# SpaceInvaders-v21.net
KiCad netlist of a schematic drawn in EAGLE
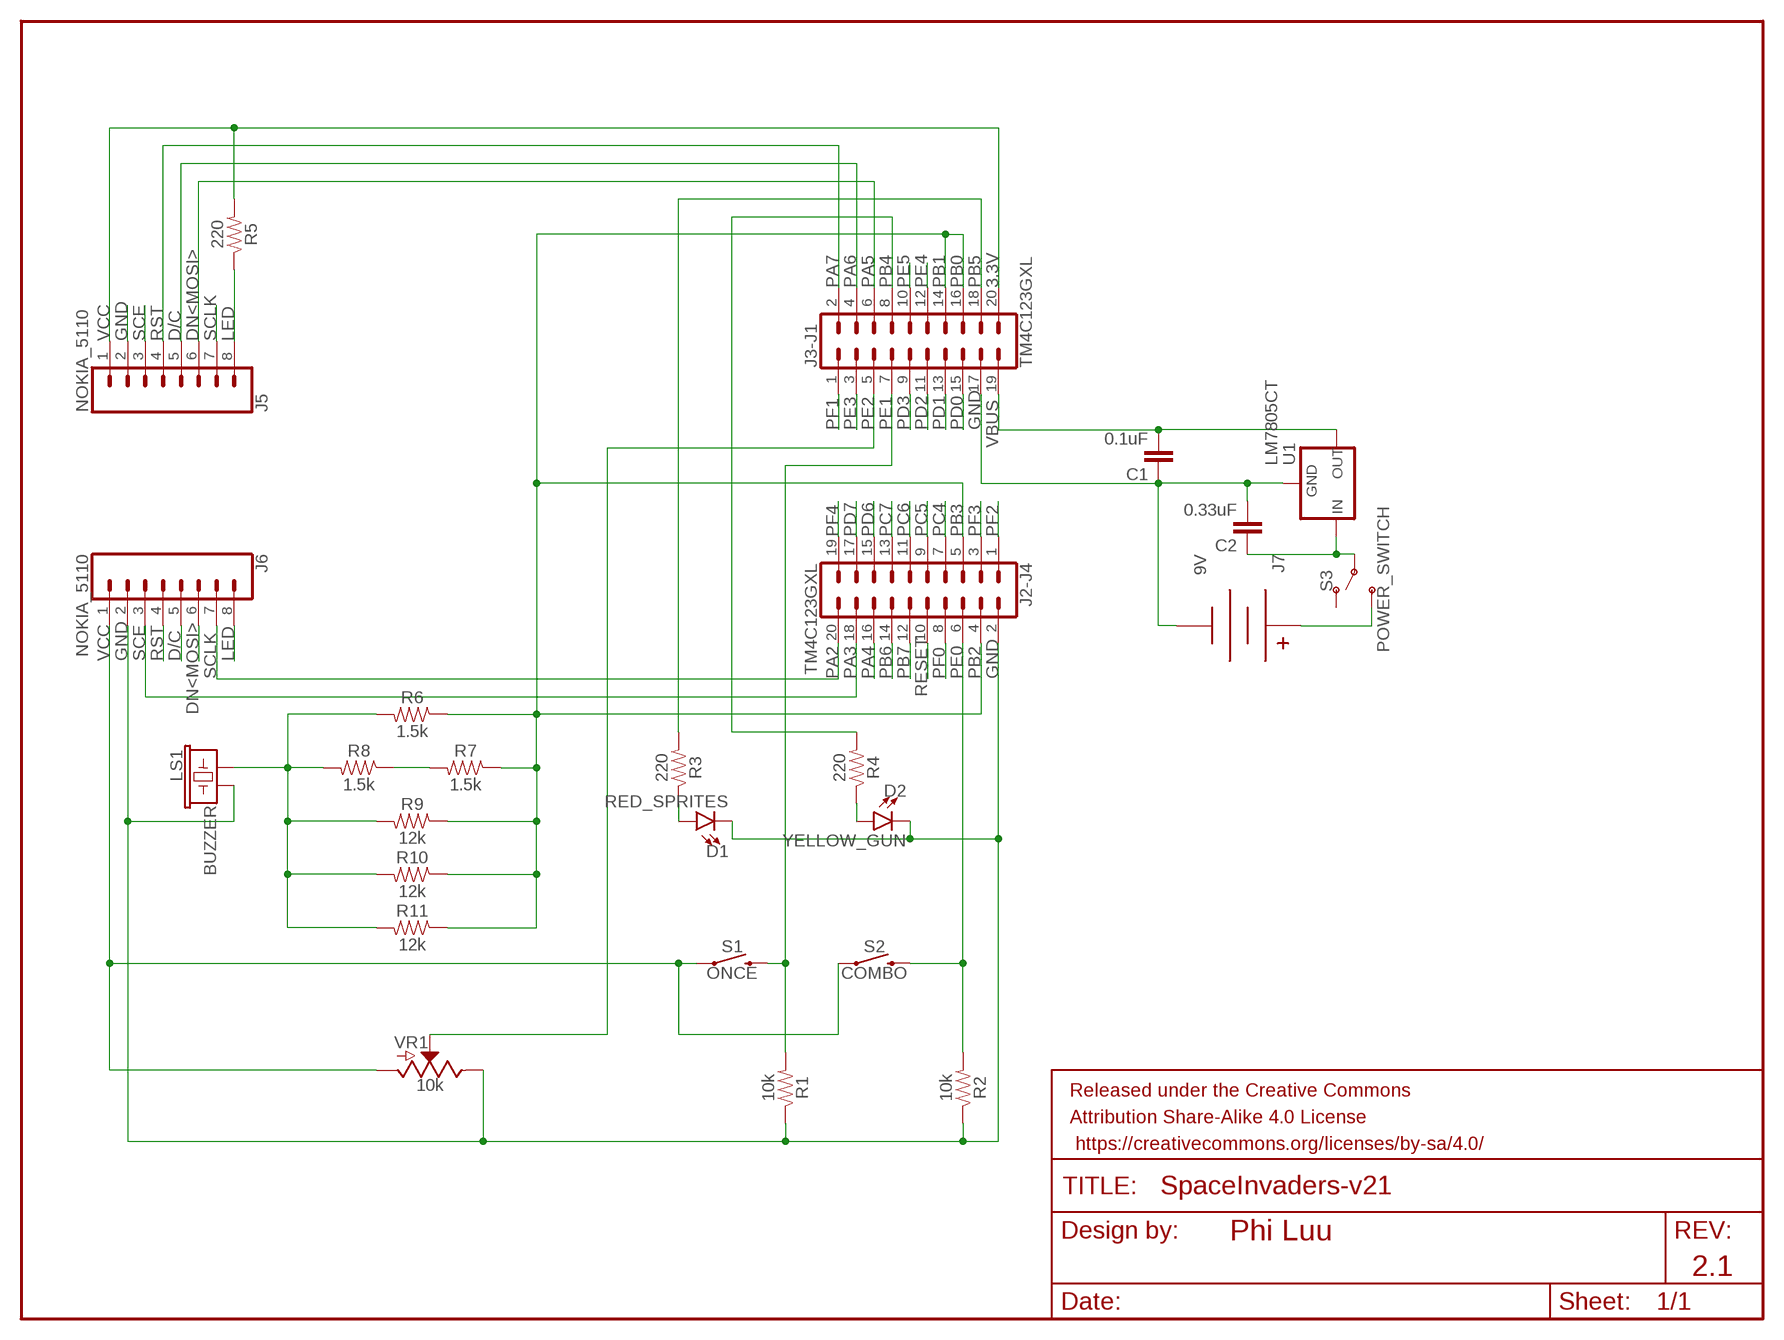
[diagram p0: schematic, sheet 1]

(export (version "E")
  (design (tool "Eeschema 10.0.6"))
  (components
    (comp (ref "C1")
      (value "0.1uF")
      (footprint "eagle-import:CAP-PTH-SMALL-KIT")
      (libsource (lib "eagle-import") (part "0.1UF-KIT-EZ-50V-20%"))
    )
    (comp (ref "C2")
      (value "0.33uF")
      (footprint "eagle-import:CAP-PTH-SMALL-KIT")
      (libsource (lib "eagle-import") (part "0.1UF-KIT-EZ-50V-20%"))
    )
    (comp (ref "D1")
      (value "RED_SPRITES")
      (footprint "eagle-import:LED_5MM")
      (libsource (lib "eagle-import") (part "LED5MM"))
    )
    (comp (ref "D2")
      (value "YELLOW_GUN")
      (footprint "eagle-import:LED_5MM")
      (libsource (lib "eagle-import") (part "LED5MM"))
    )
    (comp (ref "FRAME1")
      (value "FRAME-LETTER")
      (footprint "eagle-import:CREATIVE_COMMONS")
      (libsource (lib "eagle-import") (part "FRAME-LETTER"))
    )
    (comp (ref "J2-J4")
      (value "TM4C123GXL")
      (footprint "eagle-import:2X10")
      (libsource (lib "eagle-import") (part "CONN_10X2"))
    )
    (comp (ref "J3-J1")
      (value "TM4C123GXL")
      (footprint "eagle-import:2X10")
      (libsource (lib "eagle-import") (part "CONN_10X2"))
    )
    (comp (ref "J5")
      (value "NOKIA_5110")
      (footprint "eagle-import:1X08")
      (libsource (lib "eagle-import") (part "CONN_08{dblquote}"))
    )
    (comp (ref "J6")
      (value "NOKIA_5110")
      (footprint "eagle-import:1X08")
      (libsource (lib "eagle-import") (part "CONN_08{dblquote}"))
    )
    (comp (ref "J7")
      (value "9V")
      (footprint "eagle-import:BC9VPC")
      (libsource (lib "eagle-import") (part "BC9VPC"))
    )
    (comp (ref "LS1")
      (value "BUZZER")
      (footprint "eagle-import:BUZZER-12MM")
      (libsource (lib "eagle-import") (part "BUZZER-PTH"))
    )
    (comp (ref "R1")
      (value "10k")
      (footprint "eagle-import:AXIAL-0.3")
      (libsource (lib "eagle-import") (part "10KOHM-HORIZ-1/4W-5%"))
    )
    (comp (ref "R2")
      (value "10k")
      (footprint "eagle-import:AXIAL-0.3")
      (libsource (lib "eagle-import") (part "10KOHM-HORIZ-1/4W-5%"))
    )
    (comp (ref "R3")
      (value "220")
      (footprint "eagle-import:AXIAL-0.3")
      (libsource (lib "eagle-import") (part "1KOHM-HORIZ-1/4W-5%"))
    )
    (comp (ref "R4")
      (value "220")
      (footprint "eagle-import:AXIAL-0.3")
      (libsource (lib "eagle-import") (part "1KOHM-HORIZ-1/4W-5%"))
    )
    (comp (ref "R5")
      (value "220")
      (footprint "eagle-import:AXIAL-0.3")
      (libsource (lib "eagle-import") (part "1KOHM-HORIZ-1/4W-5%"))
    )
    (comp (ref "R6")
      (value "1.5k")
      (footprint "eagle-import:AXIAL-0.3")
      (libsource (lib "eagle-import") (part "1KOHM-HORIZ-1/4W-5%"))
    )
    (comp (ref "R7")
      (value "1.5k")
      (footprint "eagle-import:AXIAL-0.3")
      (libsource (lib "eagle-import") (part "1KOHM-HORIZ-1/4W-5%"))
    )
    (comp (ref "R8")
      (value "1.5k")
      (footprint "eagle-import:AXIAL-0.3")
      (libsource (lib "eagle-import") (part "1KOHM-HORIZ-1/4W-5%"))
    )
    (comp (ref "R9")
      (value "12k")
      (footprint "eagle-import:AXIAL-0.3")
      (libsource (lib "eagle-import") (part "1KOHM-HORIZ-1/4W-5%"))
    )
    (comp (ref "R10")
      (value "12k")
      (footprint "eagle-import:AXIAL-0.3")
      (libsource (lib "eagle-import") (part "1KOHM-HORIZ-1/4W-5%"))
    )
    (comp (ref "R11")
      (value "12k")
      (footprint "eagle-import:AXIAL-0.3")
      (libsource (lib "eagle-import") (part "1KOHM-HORIZ-1/4W-5%"))
    )
    (comp (ref "S1")
      (value "ONCE")
      (footprint "eagle-import:TACTILE_SWITCH_PTH_6.0MM")
      (libsource (lib "eagle-import") (part "MOMENTARY-SWITCH-SPST-PTH-6.0MM"))
    )
    (comp (ref "S2")
      (value "COMBO")
      (footprint "eagle-import:TACTILE_SWITCH_PTH_6.0MM")
      (libsource (lib "eagle-import") (part "MOMENTARY-SWITCH-SPST-PTH-6.0MM"))
    )
    (comp (ref "S3")
      (value "POWER_SWITCH")
      (footprint "eagle-import:SWITCH_SPDT_PTH_11.6X4.0MM")
      (libsource (lib "eagle-import") (part "SWITCH-SPDT-PTH-11.6X4.0MM"))
    )
    (comp (ref "U1")
      (value "LM7805CT")
      (footprint "eagle-import:TO220-IGO")
      (libsource (lib "eagle-import") (part "V_REG_78XXSINK"))
    )
    (comp (ref "VR1")
      (value "10k")
      (footprint "eagle-import:SLIDER-MEDIUM")
      (libsource (lib "eagle-import") (part "POTENTIOMETER_SLIDE-30MM-1/10W-20%"))
    )
  )
  (nets
    (net (code "1") (name "/3.3V") (class "Default")
      (node (ref "J3-J1") (pin "20") (pinfunction "20_20") (pintype "passive"))
      (node (ref "J5") (pin "1") (pinfunction "1_1") (pintype "passive"))
      (node (ref "J6") (pin "1") (pinfunction "1_1") (pintype "passive"))
      (node (ref "R5") (pin "P$2") (pinfunction "2_P$2") (pintype "passive"))
      (node (ref "S1") (pin "1") (pinfunction "1_1") (pintype "passive"))
      (node (ref "S2") (pin "1") (pinfunction "1_1") (pintype "passive"))
      (node (ref "VR1") (pin "BOTTOM") (pinfunction "A_BOTTOM") (pintype "passive"))
    )
    (net (code "2") (name "/GND") (class "Default")
      (node (ref "C1") (pin "1") (pinfunction "1_1") (pintype "passive"))
      (node (ref "C2") (pin "2") (pinfunction "2_2") (pintype "passive"))
      (node (ref "D1") (pin "K") (pinfunction "C_K") (pintype "passive"))
      (node (ref "D2") (pin "K") (pinfunction "C_K") (pintype "passive"))
      (node (ref "J2-J4") (pin "2") (pinfunction "2_2") (pintype "passive"))
      (node (ref "J3-J1") (pin "17") (pinfunction "17_17") (pintype "passive"))
      (node (ref "J5") (pin "2") (pinfunction "2_2") (pintype "passive"))
      (node (ref "J6") (pin "2") (pinfunction "2_2") (pintype "passive"))
      (node (ref "J7") (pin "V-") (pinfunction "V-_V-") (pintype "bidirectional"))
      (node (ref "LS1") (pin "-") (pinfunction "2_-") (pintype "passive"))
      (node (ref "R1") (pin "P$1") (pinfunction "1_P$1") (pintype "passive"))
      (node (ref "R2") (pin "P$1") (pinfunction "1_P$1") (pintype "passive"))
      (node (ref "U1") (pin "GND") (pinfunction "GND_GND") (pintype "input"))
      (node (ref "VR1") (pin "TOP") (pinfunction "E_TOP") (pintype "passive"))
    )
    (net (code "3") (name "/LED") (class "Default")
      (node (ref "J5") (pin "8") (pinfunction "8_8") (pintype "passive"))
      (node (ref "J6") (pin "8") (pinfunction "8_8") (pintype "passive"))
      (node (ref "R5") (pin "P$1") (pinfunction "1_P$1") (pintype "passive"))
    )
    (net (code "4") (name "/PA2") (class "Default")
      (node (ref "J2-J4") (pin "20") (pinfunction "20_20") (pintype "passive"))
      (node (ref "J5") (pin "7") (pinfunction "7_7") (pintype "passive"))
      (node (ref "J6") (pin "7") (pinfunction "7_7") (pintype "passive"))
    )
    (net (code "5") (name "/PA3") (class "Default")
      (node (ref "J2-J4") (pin "18") (pinfunction "18_18") (pintype "passive"))
      (node (ref "J5") (pin "3") (pinfunction "3_3") (pintype "passive"))
      (node (ref "J6") (pin "3") (pinfunction "3_3") (pintype "passive"))
    )
    (net (code "6") (name "/PA4") (class "Default")
      (node (ref "J2-J4") (pin "16") (pinfunction "16_16") (pintype "passive"))
    )
    (net (code "7") (name "/PA5") (class "Default")
      (node (ref "J3-J1") (pin "6") (pinfunction "6_6") (pintype "passive"))
      (node (ref "J5") (pin "6") (pinfunction "6_6") (pintype "passive"))
      (node (ref "J6") (pin "6") (pinfunction "6_6") (pintype "passive"))
    )
    (net (code "8") (name "/PA6") (class "Default")
      (node (ref "J3-J1") (pin "4") (pinfunction "4_4") (pintype "passive"))
      (node (ref "J5") (pin "5") (pinfunction "5_5") (pintype "passive"))
      (node (ref "J6") (pin "5") (pinfunction "5_5") (pintype "passive"))
    )
    (net (code "9") (name "/PA7") (class "Default")
      (node (ref "J3-J1") (pin "2") (pinfunction "2_2") (pintype "passive"))
      (node (ref "J5") (pin "4") (pinfunction "4_4") (pintype "passive"))
      (node (ref "J6") (pin "4") (pinfunction "4_4") (pintype "passive"))
    )
    (net (code "10") (name "/PB4") (class "Default")
      (node (ref "J3-J1") (pin "8") (pinfunction "8_8") (pintype "passive"))
      (node (ref "R4") (pin "P$2") (pinfunction "2_P$2") (pintype "passive"))
    )
    (net (code "11") (name "/PB5") (class "Default")
      (node (ref "J3-J1") (pin "18") (pinfunction "18_18") (pintype "passive"))
      (node (ref "R3") (pin "P$2") (pinfunction "2_P$2") (pintype "passive"))
    )
    (net (code "12") (name "/PB6") (class "Default")
      (node (ref "J2-J4") (pin "14") (pinfunction "14_14") (pintype "passive"))
    )
    (net (code "13") (name "/PB7") (class "Default")
      (node (ref "J2-J4") (pin "12") (pinfunction "12_12") (pintype "passive"))
    )
    (net (code "14") (name "/PC4") (class "Default")
      (node (ref "J2-J4") (pin "7") (pinfunction "7_7") (pintype "passive"))
    )
    (net (code "15") (name "/PC5") (class "Default")
      (node (ref "J2-J4") (pin "9") (pinfunction "9_9") (pintype "passive"))
    )
    (net (code "16") (name "/PC6") (class "Default")
      (node (ref "J2-J4") (pin "11") (pinfunction "11_11") (pintype "passive"))
    )
    (net (code "17") (name "/PC7") (class "Default")
      (node (ref "J2-J4") (pin "13") (pinfunction "13_13") (pintype "passive"))
    )
    (net (code "18") (name "/PD0") (class "Default")
      (node (ref "J3-J1") (pin "15") (pinfunction "15_15") (pintype "passive"))
    )
    (net (code "19") (name "/PD1") (class "Default")
      (node (ref "J3-J1") (pin "13") (pinfunction "13_13") (pintype "passive"))
    )
    (net (code "20") (name "/PD2") (class "Default")
      (node (ref "J3-J1") (pin "11") (pinfunction "11_11") (pintype "passive"))
    )
    (net (code "21") (name "/PD3") (class "Default")
      (node (ref "J3-J1") (pin "9") (pinfunction "9_9") (pintype "passive"))
    )
    (net (code "22") (name "/PD6") (class "Default")
      (node (ref "J2-J4") (pin "15") (pinfunction "15_15") (pintype "passive"))
    )
    (net (code "23") (name "/PD7") (class "Default")
      (node (ref "J2-J4") (pin "17") (pinfunction "17_17") (pintype "passive"))
    )
    (net (code "24") (name "/PE0") (class "Default")
      (node (ref "J2-J4") (pin "6") (pinfunction "6_6") (pintype "passive"))
      (node (ref "R2") (pin "P$2") (pinfunction "2_P$2") (pintype "passive"))
      (node (ref "S2") (pin "3") (pinfunction "2_3") (pintype "passive"))
    )
    (net (code "25") (name "/PE1") (class "Default")
      (node (ref "J3-J1") (pin "7") (pinfunction "7_7") (pintype "passive"))
      (node (ref "R1") (pin "P$2") (pinfunction "2_P$2") (pintype "passive"))
      (node (ref "S1") (pin "3") (pinfunction "2_3") (pintype "passive"))
    )
    (net (code "26") (name "/PE2") (class "Default")
      (node (ref "J3-J1") (pin "5") (pinfunction "5_5") (pintype "passive"))
      (node (ref "VR1") (pin "WIPER") (pinfunction "S_WIPER") (pintype "passive"))
    )
    (net (code "27") (name "/PE3") (class "Default")
      (node (ref "J3-J1") (pin "3") (pinfunction "3_3") (pintype "passive"))
    )
    (net (code "28") (name "/PE4") (class "Default")
      (node (ref "J3-J1") (pin "12") (pinfunction "12_12") (pintype "passive"))
    )
    (net (code "29") (name "/PE5") (class "Default")
      (node (ref "J3-J1") (pin "10") (pinfunction "10_10") (pintype "passive"))
    )
    (net (code "30") (name "/PF0") (class "Default")
      (node (ref "J2-J4") (pin "8") (pinfunction "8_8") (pintype "passive"))
    )
    (net (code "31") (name "/PF1") (class "Default")
      (node (ref "J3-J1") (pin "1") (pinfunction "1_1") (pintype "passive"))
    )
    (net (code "32") (name "/PF2") (class "Default")
      (node (ref "J2-J4") (pin "1") (pinfunction "1_1") (pintype "passive"))
    )
    (net (code "33") (name "/PF3") (class "Default")
      (node (ref "J2-J4") (pin "3") (pinfunction "3_3") (pintype "passive"))
    )
    (net (code "34") (name "/PF4") (class "Default")
      (node (ref "J2-J4") (pin "19") (pinfunction "19_19") (pintype "passive"))
    )
    (net (code "35") (name "/RESET") (class "Default")
      (node (ref "J2-J4") (pin "10") (pinfunction "10_10") (pintype "passive"))
    )
    (net (code "36") (name "/VBUS") (class "Default")
      (node (ref "C1") (pin "2") (pinfunction "2_2") (pintype "passive"))
      (node (ref "J3-J1") (pin "19") (pinfunction "19_19") (pintype "passive"))
      (node (ref "U1") (pin "OUT") (pinfunction "OUT_OUT") (pintype "passive"))
    )
    (net (code "37") (name "Net-(LS1-1)") (class "Default")
      (node (ref "LS1") (pin "+") (pinfunction "1_+") (pintype "passive"))
      (node (ref "R10") (pin "P$2") (pinfunction "2_P$2") (pintype "passive"))
      (node (ref "R11") (pin "P$2") (pinfunction "2_P$2") (pintype "passive"))
      (node (ref "R6") (pin "P$2") (pinfunction "2_P$2") (pintype "passive"))
      (node (ref "R8") (pin "P$2") (pinfunction "2_P$2") (pintype "passive"))
      (node (ref "R9") (pin "P$2") (pinfunction "2_P$2") (pintype "passive"))
    )
    (net (code "38") (name "Net-(R3-1)") (class "Default")
      (node (ref "D1") (pin "A") (pinfunction "A_A") (pintype "passive"))
      (node (ref "R3") (pin "P$1") (pinfunction "1_P$1") (pintype "passive"))
    )
    (net (code "39") (name "Net-(R4-1)") (class "Default")
      (node (ref "D2") (pin "A") (pinfunction "A_A") (pintype "passive"))
      (node (ref "R4") (pin "P$1") (pinfunction "1_P$1") (pintype "passive"))
    )
    (net (code "40") (name "Net-(R7-2)") (class "Default")
      (node (ref "R7") (pin "P$2") (pinfunction "2_P$2") (pintype "passive"))
      (node (ref "R8") (pin "P$1") (pinfunction "1_P$1") (pintype "passive"))
    )
    (net (code "41") (name "Net-(R10-1)") (class "Default")
      (node (ref "J2-J4") (pin "4") (pinfunction "4_4") (pintype "passive"))
      (node (ref "J2-J4") (pin "5") (pinfunction "5_5") (pintype "passive"))
      (node (ref "J3-J1") (pin "14") (pinfunction "14_14") (pintype "passive"))
      (node (ref "J3-J1") (pin "16") (pinfunction "16_16") (pintype "passive"))
      (node (ref "R10") (pin "P$1") (pinfunction "1_P$1") (pintype "passive"))
      (node (ref "R11") (pin "P$1") (pinfunction "1_P$1") (pintype "passive"))
      (node (ref "R6") (pin "P$1") (pinfunction "1_P$1") (pintype "passive"))
      (node (ref "R7") (pin "P$1") (pinfunction "1_P$1") (pintype "passive"))
      (node (ref "R9") (pin "P$1") (pinfunction "1_P$1") (pintype "passive"))
    )
    (net (code "42") (name "Net-(S3-P)") (class "Default")
      (node (ref "C2") (pin "1") (pinfunction "1_1") (pintype "passive"))
      (node (ref "S3") (pin "2") (pinfunction "P_2") (pintype "passive"))
      (node (ref "U1") (pin "IN") (pinfunction "IN_IN") (pintype "input"))
    )
    (net (code "43") (name "Net-(S3-S)") (class "Default")
      (node (ref "J7") (pin "V+") (pinfunction "V+_V+") (pintype "bidirectional"))
      (node (ref "S3") (pin "3") (pinfunction "S_3") (pintype "passive"))
    )
    (net (code "44") (name "unconnected-(S3-O-Pad1)") (class "Default")
      (node (ref "S3") (pin "1") (pinfunction "O_1") (pintype "passive"))
    )
  )
)
